# untitled.net
KiCad netlist of a schematic drawn in EAGLE
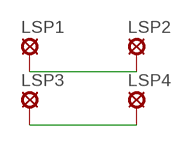
[diagram p0: schematic, sheet 1]

(export (version "E")
  (design (tool "Eeschema 10.0.6"))
  (components
    (comp (ref "LSP1")
      (value "SE13")
      (footprint "eagle-import:SE13")
      (libsource (lib "eagle-import") (part "SE13"))
    )
    (comp (ref "LSP2")
      (value "SE13")
      (footprint "eagle-import:SE13")
      (libsource (lib "eagle-import") (part "SE13"))
    )
    (comp (ref "LSP3")
      (value "SE13")
      (footprint "eagle-import:SE13")
      (libsource (lib "eagle-import") (part "SE13"))
    )
    (comp (ref "LSP4")
      (value "SE13")
      (footprint "eagle-import:SE13")
      (libsource (lib "eagle-import") (part "SE13"))
    )
  )
  (nets
    (net (code "1") (name "Net-(LSP1-PadMP)") (class "Default")
      (node (ref "LSP1") (pin "MP") (pinfunction "MP_MP") (pintype "passive"))
      (node (ref "LSP2") (pin "MP") (pinfunction "MP_MP") (pintype "passive"))
    )
    (net (code "2") (name "Net-(LSP3-PadMP)") (class "Default")
      (node (ref "LSP3") (pin "MP") (pinfunction "MP_MP") (pintype "passive"))
      (node (ref "LSP4") (pin "MP") (pinfunction "MP_MP") (pintype "passive"))
    )
  )
)
